# RPi-HAT_BUS-Controller_V0_2.net
KiCad netlist of a schematic drawn in EAGLE
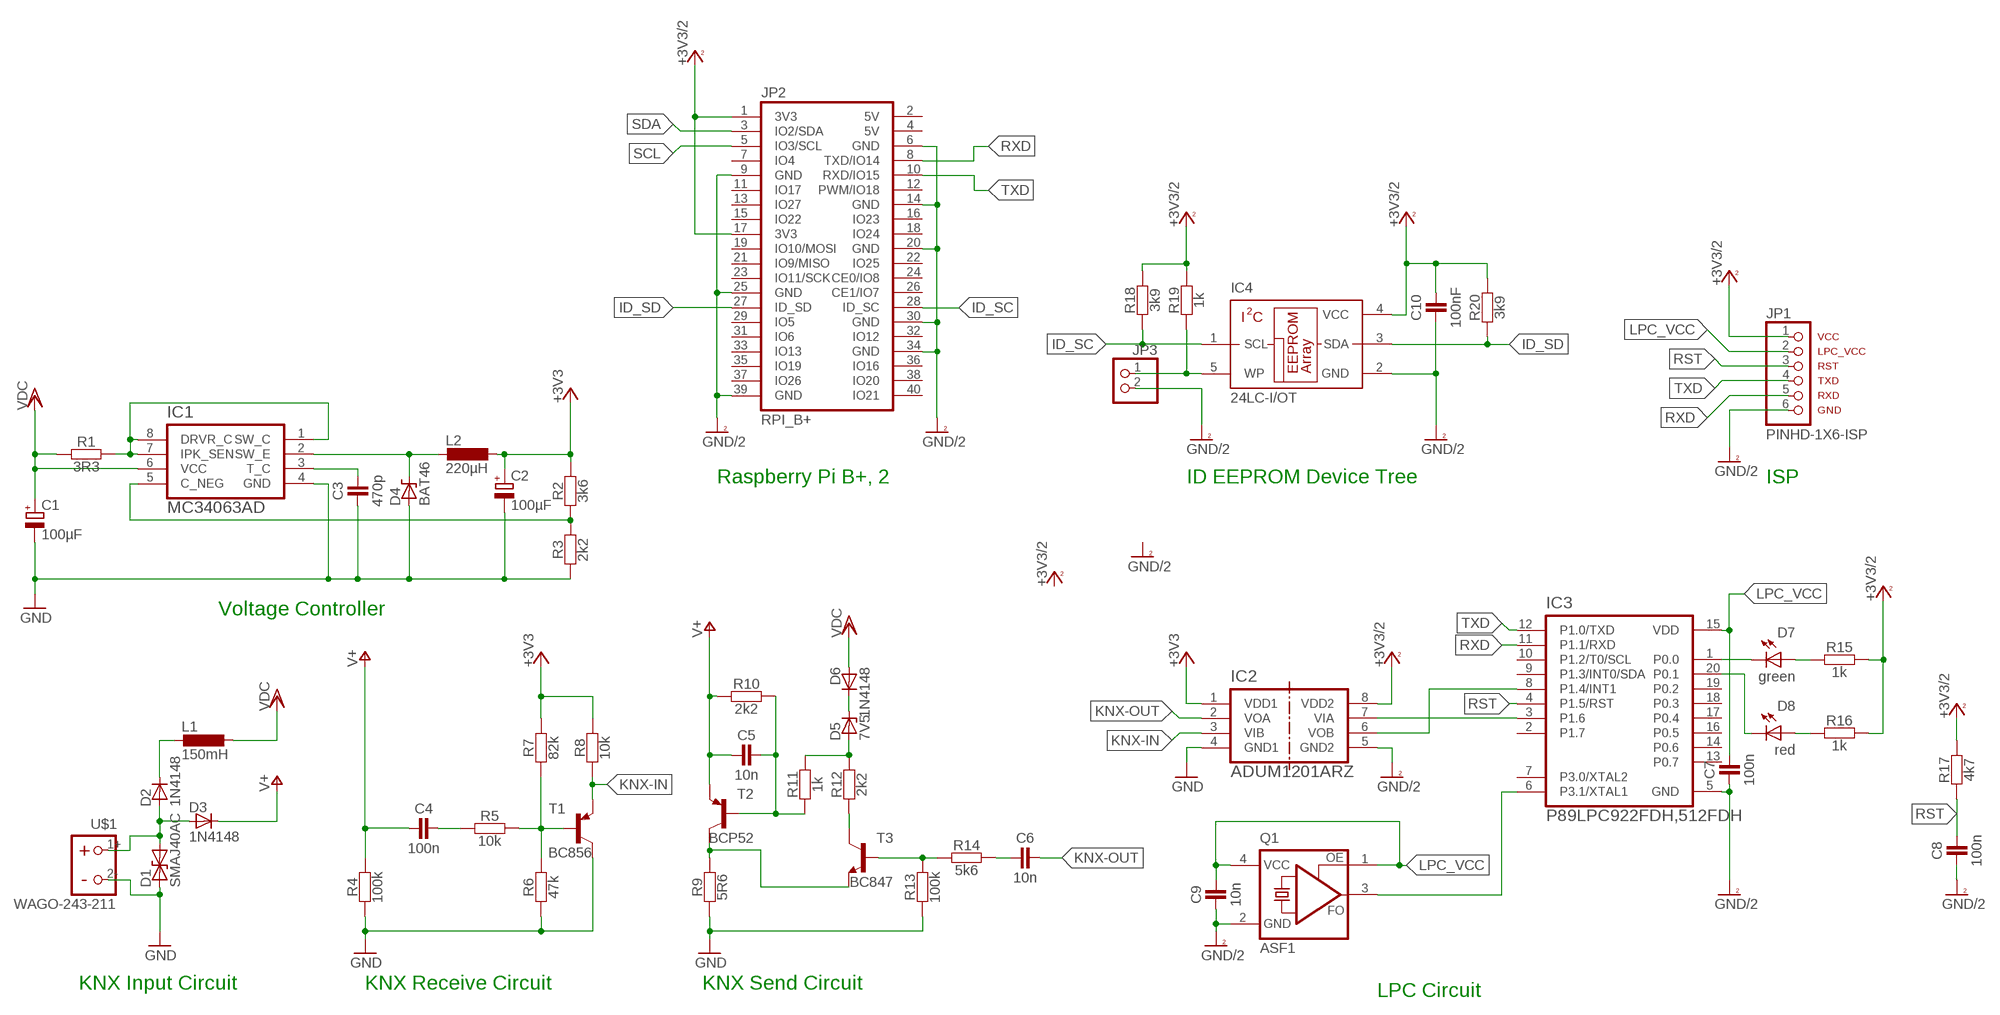
[diagram p0: schematic, sheet 1]

(export (version "E")
  (design (tool "Eeschema 10.0.6"))
  (components
    (comp (ref "C1")
      (value "100µF")
      (footprint "eagle-import:PANASONIC_D")
      (libsource (lib "eagle-import") (part "100µF,35V"))
    )
    (comp (ref "C2")
      (value "100µF")
      (footprint "eagle-import:PANASONIC_C")
      (libsource (lib "eagle-import") (part "100µF,6.3V"))
    )
    (comp (ref "C3")
      (value "470p")
      (footprint "eagle-import:R1206")
      (libsource (lib "eagle-import") (part "CAPACITORC1206"))
    )
    (comp (ref "C4")
      (value "100n")
      (footprint "eagle-import:R1206")
      (libsource (lib "eagle-import") (part "CAPACITORC1206"))
    )
    (comp (ref "C5")
      (value "10n")
      (footprint "eagle-import:R1206")
      (libsource (lib "eagle-import") (part "CAPACITORC1206"))
    )
    (comp (ref "C6")
      (value "10n")
      (footprint "eagle-import:R1206")
      (libsource (lib "eagle-import") (part "CAPACITORC1206"))
    )
    (comp (ref "C7")
      (value "100n")
      (footprint "eagle-import:R1206")
      (libsource (lib "eagle-import") (part "CAPACITORC1206"))
    )
    (comp (ref "C8")
      (value "100n")
      (footprint "eagle-import:R1206")
      (libsource (lib "eagle-import") (part "CAPACITORC1206"))
    )
    (comp (ref "C9")
      (value "10n")
      (footprint "eagle-import:R1206")
      (libsource (lib "eagle-import") (part "CAPACITORC1206"))
    )
    (comp (ref "C10")
      (value "100nF")
      (footprint "eagle-import:R1206")
      (libsource (lib "eagle-import") (part "CAPACITORC1206"))
    )
    (comp (ref "D1")
      (value "SMAJ40AC")
      (footprint "eagle-import:DO-214AC")
      (libsource (lib "eagle-import") (part "SMAJ40AC"))
    )
    (comp (ref "D2")
      (value "1N4148")
      (footprint "eagle-import:MINIMELF")
      (libsource (lib "eagle-import") (part "1N4148MINIMELF"))
    )
    (comp (ref "D3")
      (value "1N4148")
      (footprint "eagle-import:MINIMELF")
      (libsource (lib "eagle-import") (part "1N4148MINIMELF"))
    )
    (comp (ref "D4")
      (value "BAT46")
      (footprint "eagle-import:MINIMELF")
      (libsource (lib "eagle-import") (part "BAT46"))
    )
    (comp (ref "D5")
      (value "7V5")
      (footprint "eagle-import:MINIMELF")
      (libsource (lib "eagle-import") (part "Z-DIODE"))
    )
    (comp (ref "D6")
      (value "1N4148")
      (footprint "eagle-import:MINIMELF")
      (libsource (lib "eagle-import") (part "Diode_for_Selfbus-Projects_1N4148MINIMELF"))
    )
    (comp (ref "D7")
      (value "green")
      (footprint "eagle-import:CHIPLED_1206")
      (libsource (lib "eagle-import") (part "LED1206"))
    )
    (comp (ref "D8")
      (value "red")
      (footprint "eagle-import:CHIPLED_1206")
      (libsource (lib "eagle-import") (part "LED1206"))
    )
    (comp (ref "IC1")
      (value "MC34063AD")
      (footprint "eagle-import:SOIC127P600X175-8N")
      (libsource (lib "eagle-import") (part "MC34063AD"))
    )
    (comp (ref "IC2")
      (value "ADUM1201ARZ")
      (footprint "eagle-import:SOIC127P600X175-8N")
      (libsource (lib "eagle-import") (part "ADUM1201ARZ"))
    )
    (comp (ref "IC3")
      (value "P89LPC922FDH,512FDH")
      (footprint "eagle-import:SOP65P640X110-20N")
      (fields (field (name "MPN") "P89LPC922FDH,512"))
      (libsource (lib "eagle-import") (part "P89LPC922FDH,512FDH"))
    )
    (comp (ref "IC4")
      (value "24LC-I/OT")
      (footprint "eagle-import:SOT23-5")
      (libsource (lib "eagle-import") (part "24LC-I/OT"))
    )
    (comp (ref "JP1")
      (value "PINHD-1X6-ISP")
      (footprint "eagle-import:1X06")
      (libsource (lib "eagle-import") (part "PINHD-1X6-ISP"))
    )
    (comp (ref "JP2")
      (value "RPI_B+")
      (footprint "eagle-import:RPI-B+HAT")
      (libsource (lib "eagle-import") (part "RPI_B+"))
    )
    (comp (ref "JP3")
      (value "PINHD-1X2")
      (footprint "eagle-import:1X02")
      (libsource (lib "eagle-import") (part "PINHD-1X2"))
    )
    (comp (ref "L1")
      (value "150mH")
      (footprint "eagle-import:11P-L1")
      (libsource (lib "eagle-import") (part "150MH-L11PL1"))
    )
    (comp (ref "L2")
      (value "220µH")
      (footprint "eagle-import:2200-11.43")
      (libsource (lib "eagle-import") (part "220µH-SMCC11.43"))
    )
    (comp (ref "Q1")
      (value "ASF1")
      (footprint "eagle-import:ASF")
      (libsource (lib "eagle-import") (part "ASF1"))
    )
    (comp (ref "R1")
      (value "3R3")
      (footprint "eagle-import:R1206")
      (libsource (lib "eagle-import") (part "RESISTORR1206"))
    )
    (comp (ref "R2")
      (value "3k6")
      (footprint "eagle-import:R1206")
      (libsource (lib "eagle-import") (part "RESISTORR1206"))
    )
    (comp (ref "R3")
      (value "2k2")
      (footprint "eagle-import:R1206")
      (libsource (lib "eagle-import") (part "RESISTORR1206"))
    )
    (comp (ref "R4")
      (value "100k")
      (footprint "eagle-import:R1206")
      (libsource (lib "eagle-import") (part "RESISTORR1206"))
    )
    (comp (ref "R5")
      (value "10k")
      (footprint "eagle-import:R1206")
      (libsource (lib "eagle-import") (part "RESISTORR1206"))
    )
    (comp (ref "R6")
      (value "47k")
      (footprint "eagle-import:R1206")
      (libsource (lib "eagle-import") (part "RESISTORR1206"))
    )
    (comp (ref "R7")
      (value "82k")
      (footprint "eagle-import:R1206")
      (libsource (lib "eagle-import") (part "RESISTORR1206"))
    )
    (comp (ref "R8")
      (value "10k")
      (footprint "eagle-import:R1206")
      (libsource (lib "eagle-import") (part "RESISTORR1206"))
    )
    (comp (ref "R9")
      (value "5R6")
      (footprint "eagle-import:R1206")
      (libsource (lib "eagle-import") (part "RESISTORR1206"))
    )
    (comp (ref "R10")
      (value "2k2")
      (footprint "eagle-import:R1206")
      (libsource (lib "eagle-import") (part "RESISTORR1206"))
    )
    (comp (ref "R11")
      (value "1k")
      (footprint "eagle-import:R1206")
      (libsource (lib "eagle-import") (part "RESISTORR1206"))
    )
    (comp (ref "R12")
      (value "2k2")
      (footprint "eagle-import:R1206")
      (libsource (lib "eagle-import") (part "RESISTORR1206"))
    )
    (comp (ref "R13")
      (value "100k")
      (footprint "eagle-import:R1206")
      (libsource (lib "eagle-import") (part "RESISTORR1206"))
    )
    (comp (ref "R14")
      (value "5k6")
      (footprint "eagle-import:R1206")
      (libsource (lib "eagle-import") (part "RESISTORR1206"))
    )
    (comp (ref "R15")
      (value "1k")
      (footprint "eagle-import:R1206")
      (libsource (lib "eagle-import") (part "RESISTORR1206"))
    )
    (comp (ref "R16")
      (value "1k")
      (footprint "eagle-import:R1206")
      (libsource (lib "eagle-import") (part "RESISTORR1206"))
    )
    (comp (ref "R17")
      (value "4k7")
      (footprint "eagle-import:R1206")
      (libsource (lib "eagle-import") (part "RESISTORR1206"))
    )
    (comp (ref "R18")
      (value "3k9")
      (footprint "eagle-import:R1206")
      (libsource (lib "eagle-import") (part "RESISTORR1206"))
    )
    (comp (ref "R19")
      (value "1k")
      (footprint "eagle-import:R1206")
      (libsource (lib "eagle-import") (part "RESISTORR1206"))
    )
    (comp (ref "R20")
      (value "3k9")
      (footprint "eagle-import:R1206")
      (libsource (lib "eagle-import") (part "RESISTORR1206"))
    )
    (comp (ref "T1")
      (value "BC856")
      (footprint "eagle-import:SOT23")
      (libsource (lib "eagle-import") (part "PNPBC856"))
    )
    (comp (ref "T2")
      (value "BCP52")
      (footprint "eagle-import:SOT223")
      (libsource (lib "eagle-import") (part "PNPBCP52"))
    )
    (comp (ref "T3")
      (value "BC847")
      (footprint "eagle-import:SOT23")
      (libsource (lib "eagle-import") (part "NPN-BC847"))
    )
    (comp (ref "U$1")
      (value "WAGO-243-211")
      (footprint "eagle-import:WAGO-243-211")
      (libsource (lib "eagle-import") (part "WAGO-243-211"))
    )
  )
  (nets
    (net (code "1") (name "+3V3") (class "Default")
      (node (ref "C2") (pin "+") (pinfunction "+_+") (pintype "passive"))
      (node (ref "IC2") (pin "1") (pinfunction "VDD1_1") (pintype "power_in"))
      (node (ref "L2") (pin "1") (pinfunction "1_1") (pintype "passive"))
      (node (ref "R2") (pin "2") (pinfunction "2_2") (pintype "passive"))
      (node (ref "R7") (pin "2") (pinfunction "2_2") (pintype "passive"))
      (node (ref "R8") (pin "2") (pinfunction "2_2") (pintype "passive"))
    )
    (net (code "2") (name "+3V3{slash}2") (class "Default")
      (node (ref "C10") (pin "2") (pinfunction "2_2") (pintype "passive"))
      (node (ref "IC2") (pin "8") (pinfunction "VDD2_8") (pintype "power_in"))
      (node (ref "IC4") (pin "4") (pinfunction "VCC_4") (pintype "power_in"))
      (node (ref "JP1") (pin "1") (pinfunction "1_1") (pintype "passive"))
      (node (ref "JP2") (pin "1") (pinfunction "3V3_1") (pintype "passive"))
      (node (ref "JP2") (pin "17") (pinfunction "3V3_17") (pintype "passive"))
      (node (ref "R15") (pin "2") (pinfunction "2_2") (pintype "passive"))
      (node (ref "R16") (pin "2") (pinfunction "2_2") (pintype "passive"))
      (node (ref "R17") (pin "2") (pinfunction "2_2") (pintype "passive"))
      (node (ref "R18") (pin "2") (pinfunction "2_2") (pintype "passive"))
      (node (ref "R19") (pin "2") (pinfunction "2_2") (pintype "passive"))
      (node (ref "R20") (pin "2") (pinfunction "2_2") (pintype "passive"))
    )
    (net (code "3") (name "GND") (class "Default")
      (node (ref "C1") (pin "-") (pinfunction "-_-") (pintype "passive"))
      (node (ref "C2") (pin "-") (pinfunction "-_-") (pintype "passive"))
      (node (ref "C3") (pin "1") (pinfunction "1_1") (pintype "passive"))
      (node (ref "D1") (pin "A") (pinfunction "A_A") (pintype "passive"))
      (node (ref "D4") (pin "A") (pinfunction "A_A") (pintype "passive"))
      (node (ref "IC1") (pin "4") (pinfunction "GND_4") (pintype "passive"))
      (node (ref "IC2") (pin "4") (pinfunction "GND1_4") (pintype "passive"))
      (node (ref "R13") (pin "1") (pinfunction "1_1") (pintype "passive"))
      (node (ref "R3") (pin "1") (pinfunction "1_1") (pintype "passive"))
      (node (ref "R4") (pin "1") (pinfunction "1_1") (pintype "passive"))
      (node (ref "R6") (pin "1") (pinfunction "1_1") (pintype "passive"))
      (node (ref "R9") (pin "1") (pinfunction "1_1") (pintype "passive"))
      (node (ref "T1") (pin "3") (pinfunction "C_3") (pintype "passive"))
      (node (ref "U$1") (pin "2-") (pinfunction "2-_2-") (pintype "passive"))
    )
    (net (code "4") (name "GND{slash}2") (class "Default")
      (node (ref "C10") (pin "1") (pinfunction "1_1") (pintype "passive"))
      (node (ref "C7") (pin "1") (pinfunction "1_1") (pintype "passive"))
      (node (ref "C8") (pin "1") (pinfunction "1_1") (pintype "passive"))
      (node (ref "C9") (pin "1") (pinfunction "1_1") (pintype "passive"))
      (node (ref "IC2") (pin "5") (pinfunction "GND2_5") (pintype "passive"))
      (node (ref "IC3") (pin "5") (pinfunction "GND_5") (pintype "passive"))
      (node (ref "IC4") (pin "2") (pinfunction "GND_2") (pintype "power_in"))
      (node (ref "JP1") (pin "6") (pinfunction "6_6") (pintype "passive"))
      (node (ref "JP2") (pin "14") (pinfunction "GND_14") (pintype "passive"))
      (node (ref "JP2") (pin "20") (pinfunction "GND_20") (pintype "passive"))
      (node (ref "JP2") (pin "25") (pinfunction "GND_25") (pintype "passive"))
      (node (ref "JP2") (pin "30") (pinfunction "GND_30") (pintype "bidirectional"))
      (node (ref "JP2") (pin "34") (pinfunction "GND_34") (pintype "bidirectional"))
      (node (ref "JP2") (pin "39") (pinfunction "GND_39") (pintype "bidirectional"))
      (node (ref "JP2") (pin "6") (pinfunction "GND_6") (pintype "passive"))
      (node (ref "JP2") (pin "9") (pinfunction "GND_9") (pintype "passive"))
      (node (ref "JP3") (pin "2") (pinfunction "2_2") (pintype "passive"))
      (node (ref "Q1") (pin "2") (pinfunction "GND_2") (pintype "power_in"))
    )
    (net (code "5") (name "ID_SC") (class "Default")
      (node (ref "IC4") (pin "1") (pinfunction "SCL_1") (pintype "bidirectional"))
      (node (ref "JP2") (pin "28") (pinfunction "ID_SC_28") (pintype "bidirectional"))
      (node (ref "R18") (pin "1") (pinfunction "1_1") (pintype "passive"))
    )
    (net (code "6") (name "ID_SD") (class "Default")
      (node (ref "IC4") (pin "3") (pinfunction "SDA_3") (pintype "bidirectional"))
      (node (ref "JP2") (pin "27") (pinfunction "ID_SD_27") (pintype "bidirectional"))
      (node (ref "R20") (pin "1") (pinfunction "1_1") (pintype "passive"))
    )
    (net (code "7") (name "KNX-IN") (class "Default")
      (node (ref "IC2") (pin "3") (pinfunction "VIB_3") (pintype "input"))
      (node (ref "R8") (pin "1") (pinfunction "1_1") (pintype "passive"))
      (node (ref "T1") (pin "2") (pinfunction "E_2") (pintype "passive"))
    )
    (net (code "8") (name "KNX-OUT") (class "Default")
      (node (ref "C6") (pin "2") (pinfunction "2_2") (pintype "passive"))
      (node (ref "IC2") (pin "2") (pinfunction "VOA_2") (pintype "output"))
    )
    (net (code "9") (name "LPC_VCC") (class "Default")
      (node (ref "C7") (pin "2") (pinfunction "2_2") (pintype "passive"))
      (node (ref "C9") (pin "2") (pinfunction "2_2") (pintype "passive"))
      (node (ref "IC3") (pin "15") (pinfunction "VDD_15") (pintype "power_in"))
      (node (ref "JP1") (pin "2") (pinfunction "2_2") (pintype "passive"))
      (node (ref "Q1") (pin "1") (pinfunction "OE_1") (pintype "input"))
      (node (ref "Q1") (pin "4") (pinfunction "VCC_4") (pintype "power_in"))
    )
    (net (code "10") (name "Net-(C4-Pad2)") (class "Default")
      (node (ref "C4") (pin "2") (pinfunction "2_2") (pintype "passive"))
      (node (ref "R5") (pin "1") (pinfunction "1_1") (pintype "passive"))
    )
    (net (code "11") (name "Net-(C6-Pad1)") (class "Default")
      (node (ref "C6") (pin "1") (pinfunction "1_1") (pintype "passive"))
      (node (ref "R14") (pin "2") (pinfunction "2_2") (pintype "passive"))
    )
    (net (code "12") (name "Net-(D1-PadC)") (class "Default")
      (node (ref "D1") (pin "C") (pinfunction "C_C") (pintype "passive"))
      (node (ref "D2") (pin "A") (pinfunction "A_A") (pintype "passive"))
      (node (ref "D3") (pin "A") (pinfunction "A_A") (pintype "passive"))
      (node (ref "U$1") (pin "1+") (pinfunction "1+_1+") (pintype "passive"))
    )
    (net (code "13") (name "Net-(D2-PadC)") (class "Default")
      (node (ref "D2") (pin "C") (pinfunction "C_C") (pintype "passive"))
      (node (ref "L1") (pin "2") (pinfunction "2_2") (pintype "passive"))
    )
    (net (code "14") (name "Net-(D5-PadA)") (class "Default")
      (node (ref "D5") (pin "A") (pinfunction "A_A") (pintype "passive"))
      (node (ref "R11") (pin "2") (pinfunction "2_2") (pintype "passive"))
      (node (ref "R12") (pin "2") (pinfunction "2_2") (pintype "passive"))
    )
    (net (code "15") (name "Net-(D5-PadC)") (class "Default")
      (node (ref "D5") (pin "C") (pinfunction "C_C") (pintype "passive"))
      (node (ref "D6") (pin "C") (pinfunction "C_C") (pintype "passive"))
    )
    (net (code "16") (name "Net-(D7-PadA)") (class "Default")
      (node (ref "D7") (pin "A") (pinfunction "A_A") (pintype "passive"))
      (node (ref "R15") (pin "1") (pinfunction "1_1") (pintype "passive"))
    )
    (net (code "17") (name "Net-(D8-PadA)") (class "Default")
      (node (ref "D8") (pin "A") (pinfunction "A_A") (pintype "passive"))
      (node (ref "R16") (pin "1") (pinfunction "1_1") (pintype "passive"))
    )
    (net (code "18") (name "Net-(IC1-C_NEG)") (class "Default")
      (node (ref "IC1") (pin "5") (pinfunction "C_NEG_5") (pintype "input"))
      (node (ref "R2") (pin "1") (pinfunction "1_1") (pintype "passive"))
      (node (ref "R3") (pin "2") (pinfunction "2_2") (pintype "passive"))
    )
    (net (code "19") (name "Net-(IC1-DRVR_C)") (class "Default")
      (node (ref "IC1") (pin "1") (pinfunction "SW_C_1") (pintype "output"))
      (node (ref "IC1") (pin "7") (pinfunction "IPK_SEN_7") (pintype "input"))
      (node (ref "IC1") (pin "8") (pinfunction "DRVR_C_8") (pintype "input"))
      (node (ref "R1") (pin "2") (pinfunction "2_2") (pintype "passive"))
    )
    (net (code "20") (name "Net-(IC1-SW_E)") (class "Default")
      (node (ref "D4") (pin "C") (pinfunction "C_C") (pintype "passive"))
      (node (ref "IC1") (pin "2") (pinfunction "SW_E_2") (pintype "output"))
      (node (ref "L2") (pin "2") (pinfunction "2_2") (pintype "passive"))
    )
    (net (code "21") (name "Net-(IC1-T_C)") (class "Default")
      (node (ref "C3") (pin "2") (pinfunction "2_2") (pintype "passive"))
      (node (ref "IC1") (pin "3") (pinfunction "T_C_3") (pintype "output"))
    )
    (net (code "22") (name "Net-(IC2-VIA)") (class "Default")
      (node (ref "IC2") (pin "7") (pinfunction "VIA_7") (pintype "input"))
      (node (ref "IC3") (pin "3") (pinfunction "P1.6_3") (pintype "bidirectional"))
    )
    (net (code "23") (name "Net-(IC2-VOB)") (class "Default")
      (node (ref "IC2") (pin "6") (pinfunction "VOB_6") (pintype "output"))
      (node (ref "IC3") (pin "8") (pinfunction "P1.4/INT1_8") (pintype "bidirectional"))
    )
    (net (code "24") (name "Net-(IC3-P0.0)") (class "Default")
      (node (ref "D7") (pin "C") (pinfunction "C_C") (pintype "passive"))
      (node (ref "IC3") (pin "1") (pinfunction "P0.0_1") (pintype "bidirectional"))
    )
    (net (code "25") (name "Net-(IC3-P0.1)") (class "Default")
      (node (ref "D8") (pin "C") (pinfunction "C_C") (pintype "passive"))
      (node (ref "IC3") (pin "20") (pinfunction "P0.1_20") (pintype "bidirectional"))
    )
    (net (code "26") (name "Net-(IC3-P3.1{slash}XTAL1)") (class "Default")
      (node (ref "IC3") (pin "6") (pinfunction "P3.1/XTAL1_6") (pintype "bidirectional"))
      (node (ref "Q1") (pin "3") (pinfunction "FO_3") (pintype "output"))
    )
    (net (code "27") (name "Net-(IC4-WP)") (class "Default")
      (node (ref "IC4") (pin "5") (pinfunction "WP_5") (pintype "bidirectional"))
      (node (ref "JP3") (pin "1") (pinfunction "1_1") (pintype "passive"))
      (node (ref "R19") (pin "1") (pinfunction "1_1") (pintype "passive"))
    )
    (net (code "28") (name "Net-(T1-B)") (class "Default")
      (node (ref "R5") (pin "2") (pinfunction "2_2") (pintype "passive"))
      (node (ref "R6") (pin "2") (pinfunction "2_2") (pintype "passive"))
      (node (ref "R7") (pin "1") (pinfunction "1_1") (pintype "passive"))
      (node (ref "T1") (pin "1") (pinfunction "B_1") (pintype "passive"))
    )
    (net (code "29") (name "Net-(T2-B)") (class "Default")
      (node (ref "C5") (pin "2") (pinfunction "2_2") (pintype "passive"))
      (node (ref "R10") (pin "2") (pinfunction "2_2") (pintype "passive"))
      (node (ref "R11") (pin "1") (pinfunction "1_1") (pintype "passive"))
      (node (ref "T2") (pin "1") (pinfunction "B_1") (pintype "passive"))
    )
    (net (code "30") (name "Net-(T3-B)") (class "Default")
      (node (ref "R13") (pin "2") (pinfunction "2_2") (pintype "passive"))
      (node (ref "R14") (pin "1") (pinfunction "1_1") (pintype "passive"))
      (node (ref "T3") (pin "1") (pinfunction "B_1") (pintype "passive"))
    )
    (net (code "31") (name "Net-(T3-C)") (class "Default")
      (node (ref "R12") (pin "1") (pinfunction "1_1") (pintype "passive"))
      (node (ref "T3") (pin "3") (pinfunction "C_3") (pintype "passive"))
    )
    (net (code "32") (name "Net-(T3-E)") (class "Default")
      (node (ref "R9") (pin "2") (pinfunction "2_2") (pintype "passive"))
      (node (ref "T2") (pin "2") (pinfunction "C_2") (pintype "passive"))
      (node (ref "T2") (pin "4") (pinfunction "C_4") (pintype "passive"))
      (node (ref "T3") (pin "2") (pinfunction "E_2") (pintype "passive"))
    )
    (net (code "33") (name "RST") (class "Default")
      (node (ref "C8") (pin "2") (pinfunction "2_2") (pintype "passive"))
      (node (ref "IC3") (pin "4") (pinfunction "P1.5/RST_4") (pintype "input"))
      (node (ref "JP1") (pin "3") (pinfunction "3_3") (pintype "passive"))
      (node (ref "R17") (pin "1") (pinfunction "1_1") (pintype "passive"))
    )
    (net (code "34") (name "RXD") (class "Default")
      (node (ref "IC3") (pin "11") (pinfunction "P1.1/RXD_11") (pintype "bidirectional"))
      (node (ref "JP1") (pin "5") (pinfunction "5_5") (pintype "passive"))
      (node (ref "JP2") (pin "8") (pinfunction "TXD/IO14_8") (pintype "passive"))
    )
    (net (code "35") (name "SCL") (class "Default")
      (node (ref "JP2") (pin "5") (pinfunction "IO3/SCL_5") (pintype "passive"))
    )
    (net (code "36") (name "SDA") (class "Default")
      (node (ref "JP2") (pin "3") (pinfunction "IO2/SDA_3") (pintype "passive"))
    )
    (net (code "37") (name "TXD") (class "Default")
      (node (ref "IC3") (pin "12") (pinfunction "P1.0/TXD_12") (pintype "bidirectional"))
      (node (ref "JP1") (pin "4") (pinfunction "4_4") (pintype "passive"))
      (node (ref "JP2") (pin "10") (pinfunction "RXD/IO15_10") (pintype "passive"))
    )
    (net (code "38") (name "V+") (class "Default")
      (node (ref "C4") (pin "1") (pinfunction "1_1") (pintype "passive"))
      (node (ref "C5") (pin "1") (pinfunction "1_1") (pintype "passive"))
      (node (ref "D3") (pin "C") (pinfunction "C_C") (pintype "passive"))
      (node (ref "R10") (pin "1") (pinfunction "1_1") (pintype "passive"))
      (node (ref "R4") (pin "2") (pinfunction "2_2") (pintype "passive"))
      (node (ref "T2") (pin "3") (pinfunction "E_3") (pintype "passive"))
    )
    (net (code "39") (name "VDC") (class "Default")
      (node (ref "C1") (pin "+") (pinfunction "+_+") (pintype "passive"))
      (node (ref "D6") (pin "A") (pinfunction "A_A") (pintype "passive"))
      (node (ref "IC1") (pin "6") (pinfunction "VCC_6") (pintype "power_in"))
      (node (ref "L1") (pin "1") (pinfunction "1_1") (pintype "passive"))
      (node (ref "R1") (pin "1") (pinfunction "1_1") (pintype "passive"))
    )
    (net (code "40") (name "unconnected-(IC3-P0.2-Pad19)") (class "Default")
      (node (ref "IC3") (pin "19") (pinfunction "P0.2_19") (pintype "bidirectional"))
    )
    (net (code "41") (name "unconnected-(IC3-P0.3-Pad18)") (class "Default")
      (node (ref "IC3") (pin "18") (pinfunction "P0.3_18") (pintype "bidirectional"))
    )
    (net (code "42") (name "unconnected-(IC3-P0.4-Pad17)") (class "Default")
      (node (ref "IC3") (pin "17") (pinfunction "P0.4_17") (pintype "bidirectional"))
    )
    (net (code "43") (name "unconnected-(IC3-P0.5-Pad16)") (class "Default")
      (node (ref "IC3") (pin "16") (pinfunction "P0.5_16") (pintype "bidirectional"))
    )
    (net (code "44") (name "unconnected-(IC3-P0.6-Pad14)") (class "Default")
      (node (ref "IC3") (pin "14") (pinfunction "P0.6_14") (pintype "bidirectional"))
    )
    (net (code "45") (name "unconnected-(IC3-P0.7-Pad13)") (class "Default")
      (node (ref "IC3") (pin "13") (pinfunction "P0.7_13") (pintype "passive"))
    )
    (net (code "46") (name "unconnected-(IC3-P1.2{slash}T0{slash}SCL-Pad10)") (class "Default")
      (node (ref "IC3") (pin "10") (pinfunction "P1.2/T0/SCL_10") (pintype "bidirectional"))
    )
    (net (code "47") (name "unconnected-(IC3-P1.3{slash}INT0{slash}SDA-Pad9)") (class "Default")
      (node (ref "IC3") (pin "9") (pinfunction "P1.3/INT0/SDA_9") (pintype "bidirectional"))
    )
    (net (code "48") (name "unconnected-(IC3-P1.7-Pad2)") (class "Default")
      (node (ref "IC3") (pin "2") (pinfunction "P1.7_2") (pintype "bidirectional"))
    )
    (net (code "49") (name "unconnected-(IC3-P3.0{slash}XTAL2-Pad7)") (class "Default")
      (node (ref "IC3") (pin "7") (pinfunction "P3.0/XTAL2_7") (pintype "bidirectional"))
    )
    (net (code "50") (name "unconnected-(JP2-5V-Pad2)") (class "Default")
      (node (ref "JP2") (pin "2") (pinfunction "5V_2") (pintype "passive"))
    )
    (net (code "51") (name "unconnected-(JP2-5V-Pad4)") (class "Default")
      (node (ref "JP2") (pin "4") (pinfunction "5V_4") (pintype "passive"))
    )
    (net (code "52") (name "unconnected-(JP2-CE0{slash}IO8-Pad24)") (class "Default")
      (node (ref "JP2") (pin "24") (pinfunction "CE0/IO8_24") (pintype "passive"))
    )
    (net (code "53") (name "unconnected-(JP2-CE1{slash}IO7-Pad26)") (class "Default")
      (node (ref "JP2") (pin "26") (pinfunction "CE1/IO7_26") (pintype "passive"))
    )
    (net (code "54") (name "unconnected-(JP2-IO4-Pad7)") (class "Default")
      (node (ref "JP2") (pin "7") (pinfunction "IO4_7") (pintype "passive"))
    )
    (net (code "55") (name "unconnected-(JP2-IO5-Pad29)") (class "Default")
      (node (ref "JP2") (pin "29") (pinfunction "IO5_29") (pintype "bidirectional"))
    )
    (net (code "56") (name "unconnected-(JP2-IO6-Pad31)") (class "Default")
      (node (ref "JP2") (pin "31") (pinfunction "IO6_31") (pintype "bidirectional"))
    )
    (net (code "57") (name "unconnected-(JP2-IO9{slash}MISO-Pad21)") (class "Default")
      (node (ref "JP2") (pin "21") (pinfunction "IO9/MISO_21") (pintype "passive"))
    )
    (net (code "58") (name "unconnected-(JP2-IO10{slash}MOSI-Pad19)") (class "Default")
      (node (ref "JP2") (pin "19") (pinfunction "IO10/MOSI_19") (pintype "passive"))
    )
    (net (code "59") (name "unconnected-(JP2-IO11{slash}SCK-Pad23)") (class "Default")
      (node (ref "JP2") (pin "23") (pinfunction "IO11/SCK_23") (pintype "passive"))
    )
    (net (code "60") (name "unconnected-(JP2-IO12-Pad32)") (class "Default")
      (node (ref "JP2") (pin "32") (pinfunction "IO12_32") (pintype "bidirectional"))
    )
    (net (code "61") (name "unconnected-(JP2-IO13-Pad33)") (class "Default")
      (node (ref "JP2") (pin "33") (pinfunction "IO13_33") (pintype "bidirectional"))
    )
    (net (code "62") (name "unconnected-(JP2-IO16-Pad36)") (class "Default")
      (node (ref "JP2") (pin "36") (pinfunction "IO16_36") (pintype "bidirectional"))
    )
    (net (code "63") (name "unconnected-(JP2-IO17-Pad11)") (class "Default")
      (node (ref "JP2") (pin "11") (pinfunction "IO17_11") (pintype "passive"))
    )
    (net (code "64") (name "unconnected-(JP2-IO19-Pad35)") (class "Default")
      (node (ref "JP2") (pin "35") (pinfunction "IO19_35") (pintype "bidirectional"))
    )
    (net (code "65") (name "unconnected-(JP2-IO20-Pad38)") (class "Default")
      (node (ref "JP2") (pin "38") (pinfunction "IO20_38") (pintype "bidirectional"))
    )
    (net (code "66") (name "unconnected-(JP2-IO21-Pad40)") (class "Default")
      (node (ref "JP2") (pin "40") (pinfunction "IO21_40") (pintype "bidirectional"))
    )
    (net (code "67") (name "unconnected-(JP2-IO22-Pad15)") (class "Default")
      (node (ref "JP2") (pin "15") (pinfunction "IO22_15") (pintype "passive"))
    )
    (net (code "68") (name "unconnected-(JP2-IO23-Pad16)") (class "Default")
      (node (ref "JP2") (pin "16") (pinfunction "IO23_16") (pintype "passive"))
    )
    (net (code "69") (name "unconnected-(JP2-IO24-Pad18)") (class "Default")
      (node (ref "JP2") (pin "18") (pinfunction "IO24_18") (pintype "passive"))
    )
    (net (code "70") (name "unconnected-(JP2-IO25-Pad22)") (class "Default")
      (node (ref "JP2") (pin "22") (pinfunction "IO25_22") (pintype "passive"))
    )
    (net (code "71") (name "unconnected-(JP2-IO26-Pad37)") (class "Default")
      (node (ref "JP2") (pin "37") (pinfunction "IO26_37") (pintype "bidirectional"))
    )
    (net (code "72") (name "unconnected-(JP2-IO27-Pad13)") (class "Default")
      (node (ref "JP2") (pin "13") (pinfunction "IO27_13") (pintype "passive"))
    )
    (net (code "73") (name "unconnected-(JP2-PWM{slash}IO18-Pad12)") (class "Default")
      (node (ref "JP2") (pin "12") (pinfunction "PWM/IO18_12") (pintype "passive"))
    )
  )
)
